# relayBoard.net
KiCad netlist of a schematic drawn in EAGLE
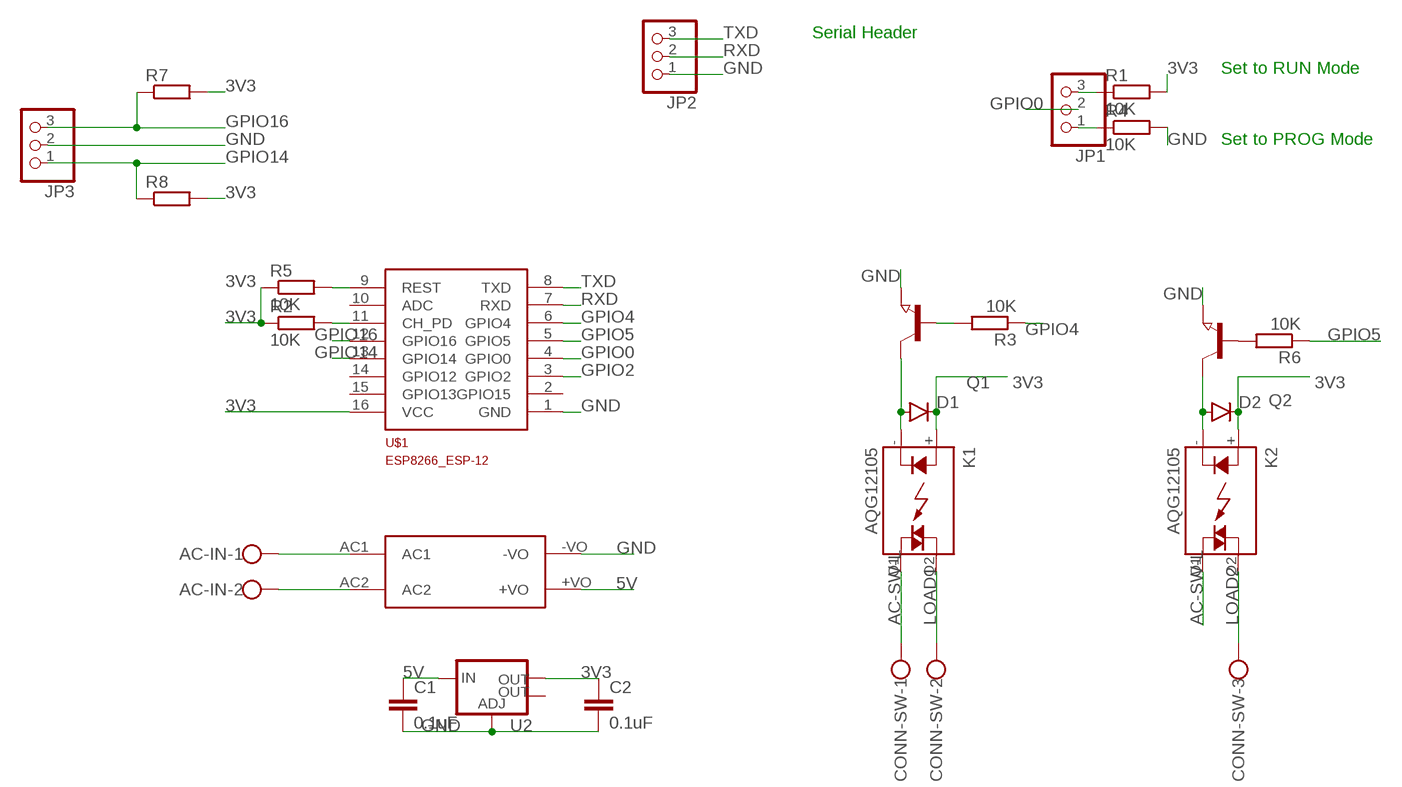
[diagram p0: schematic, sheet 1]

(export (version "E")
  (design (tool "Eeschema 10.0.6"))
  (components
    (comp (ref "AC-IN")
      (value "W237-102")
      (footprint "eagle-import:W237-102")
      (fields (field (name "MPN") "237-102"))
      (libsource (lib "eagle-import") (part "W237-102"))
    )
    (comp (ref "C1")
      (value "0.1uF")
      (footprint "eagle-import:0603-CAP")
      (libsource (lib "eagle-import") (part "0.1UF-25V-5%(0603)"))
    )
    (comp (ref "C2")
      (value "0.1uF")
      (footprint "eagle-import:0603-CAP")
      (libsource (lib "eagle-import") (part "0.1UF-25V-5%(0603)"))
    )
    (comp (ref "CONN-SW")
      (value "W237-103")
      (footprint "eagle-import:W237-103")
      (fields (field (name "MPN") "237-103"))
      (libsource (lib "eagle-import") (part "W237-103"))
    )
    (comp (ref "D1")
      (value "DIODESMA")
      (footprint "eagle-import:SMA-DIODE")
      (libsource (lib "eagle-import") (part "DIODESMA"))
    )
    (comp (ref "D2")
      (value "DIODESMA")
      (footprint "eagle-import:SMA-DIODE")
      (libsource (lib "eagle-import") (part "DIODESMA"))
    )
    (comp (ref "JP1")
      (value "PINHD-1X3")
      (footprint "eagle-import:1X03")
      (libsource (lib "eagle-import") (part "PINHD-1X3"))
    )
    (comp (ref "JP2")
      (value "PINHD-1X3")
      (footprint "eagle-import:1X03")
      (libsource (lib "eagle-import") (part "PINHD-1X3"))
    )
    (comp (ref "JP3")
      (value "PINHD-1X3")
      (footprint "eagle-import:1X03")
      (libsource (lib "eagle-import") (part "PINHD-1X3"))
    )
    (comp (ref "K1")
      (value "AQG12105")
      (footprint "eagle-import:AQG")
      (fields (field (name "MF") "AROMAT/ MATSUSHITA"))
      (libsource (lib "eagle-import") (part "AQG12105"))
    )
    (comp (ref "K2")
      (value "AQG12105")
      (footprint "eagle-import:AQG")
      (fields (field (name "MF") "AROMAT/ MATSUSHITA"))
      (libsource (lib "eagle-import") (part "AQG12105"))
    )
    (comp (ref "Q1")
      (value "NPN-TRANSISTOR_SOT23")
      (footprint "eagle-import:SOT23")
      (libsource (lib "eagle-import") (part "NPN-TRANSISTOR_SOT23"))
    )
    (comp (ref "Q2")
      (value "NPN-TRANSISTOR_SOT23")
      (footprint "eagle-import:SOT23")
      (libsource (lib "eagle-import") (part "NPN-TRANSISTOR_SOT23"))
    )
    (comp (ref "R1")
      (value "10K")
      (footprint "eagle-import:R0805")
      (libsource (lib "eagle-import") (part "R-EU_R0805"))
    )
    (comp (ref "R2")
      (value "10K")
      (footprint "eagle-import:R0805")
      (libsource (lib "eagle-import") (part "R-EU_R0805"))
    )
    (comp (ref "R3")
      (value "10K")
      (footprint "eagle-import:R0805")
      (libsource (lib "eagle-import") (part "R-EU_R0805"))
    )
    (comp (ref "R4")
      (value "10K")
      (footprint "eagle-import:R0805")
      (libsource (lib "eagle-import") (part "R-EU_R0805"))
    )
    (comp (ref "R5")
      (value "10K")
      (footprint "eagle-import:R0805")
      (libsource (lib "eagle-import") (part "R-EU_R0805"))
    )
    (comp (ref "R6")
      (value "10K")
      (footprint "eagle-import:R0805")
      (libsource (lib "eagle-import") (part "R-EU_R0805"))
    )
    (comp (ref "R7")
      (value "R-EU_R0805")
      (footprint "eagle-import:R0805")
      (libsource (lib "eagle-import") (part "R-EU_R0805"))
    )
    (comp (ref "R8")
      (value "R-EU_R0805")
      (footprint "eagle-import:R0805")
      (libsource (lib "eagle-import") (part "R-EU_R0805"))
    )
    (comp (ref "U$1")
      (value "ESP8266_ESP-12")
      (footprint "eagle-import:ESP8266-ESP12")
      (libsource (lib "eagle-import") (part "ESP8266_ESP-12"))
    )
    (comp (ref "U$4")
      (value "HLK-PM01")
      (footprint "eagle-import:HLK-PM01")
      (libsource (lib "eagle-import") (part "HLK-PM01"))
    )
    (comp (ref "U2")
      (value "V_REG_LM1117SOT223")
      (footprint "eagle-import:SOT223")
      (libsource (lib "eagle-import") (part "V_REG_LM1117SOT223"))
    )
  )
  (nets
    (net (code "1") (name "/3V3") (class "Default")
      (node (ref "C2") (pin "1") (pinfunction "1_1") (pintype "passive"))
      (node (ref "D1") (pin "C") (pinfunction "C_C") (pintype "passive"))
      (node (ref "D2") (pin "C") (pinfunction "C_C") (pintype "passive"))
      (node (ref "K1") (pin "+") (pinfunction "A_+") (pintype "passive"))
      (node (ref "K2") (pin "+") (pinfunction "A_+") (pintype "passive"))
      (node (ref "R1") (pin "2") (pinfunction "2_2") (pintype "passive"))
      (node (ref "R2") (pin "1") (pinfunction "1_1") (pintype "passive"))
      (node (ref "R5") (pin "1") (pinfunction "1_1") (pintype "passive"))
      (node (ref "R7") (pin "2") (pinfunction "2_2") (pintype "passive"))
      (node (ref "R8") (pin "2") (pinfunction "2_2") (pintype "passive"))
      (node (ref "U$1") (pin "16") (pinfunction "VCC_16") (pintype "bidirectional"))
      (node (ref "U2") (pin "2") (pinfunction "OUT_2") (pintype "output"))
    )
    (net (code "2") (name "/5V") (class "Default")
      (node (ref "C1") (pin "1") (pinfunction "1_1") (pintype "passive"))
      (node (ref "U$4") (pin "+VO") (pinfunction "+VO_+VO") (pintype "bidirectional"))
      (node (ref "U2") (pin "3") (pinfunction "IN_3") (pintype "input"))
    )
    (net (code "3") (name "/AC-SW-L") (class "Default")
      (node (ref "CONN-SW") (pin "1") (pinfunction "KL_1") (pintype "passive"))
      (node (ref "K1") (pin "O1") (pinfunction "DS2_O1") (pintype "passive"))
      (node (ref "K2") (pin "O1") (pinfunction "DS2_O1") (pintype "passive"))
    )
    (net (code "4") (name "/GND") (class "Default")
      (node (ref "C1") (pin "2") (pinfunction "2_2") (pintype "passive"))
      (node (ref "C2") (pin "2") (pinfunction "2_2") (pintype "passive"))
      (node (ref "JP2") (pin "1") (pinfunction "1_1") (pintype "passive"))
      (node (ref "JP3") (pin "2") (pinfunction "2_2") (pintype "passive"))
      (node (ref "Q1") (pin "2") (pinfunction "E_2") (pintype "passive"))
      (node (ref "Q2") (pin "2") (pinfunction "E_2") (pintype "passive"))
      (node (ref "R4") (pin "2") (pinfunction "2_2") (pintype "passive"))
      (node (ref "U$1") (pin "1") (pinfunction "GND_1") (pintype "bidirectional"))
      (node (ref "U$4") (pin "-VO") (pinfunction "-VO_-VO") (pintype "bidirectional"))
      (node (ref "U2") (pin "1") (pinfunction "ADJ_1") (pintype "input"))
    )
    (net (code "5") (name "/GPIO0") (class "Default")
      (node (ref "JP1") (pin "2") (pinfunction "2_2") (pintype "passive"))
      (node (ref "U$1") (pin "4") (pinfunction "GPIO0_4") (pintype "bidirectional"))
    )
    (net (code "6") (name "/GPIO2") (class "Default")
      (node (ref "U$1") (pin "3") (pinfunction "GPIO2_3") (pintype "bidirectional"))
    )
    (net (code "7") (name "/GPIO4") (class "Default")
      (node (ref "R3") (pin "1") (pinfunction "1_1") (pintype "passive"))
      (node (ref "U$1") (pin "6") (pinfunction "GPIO4_6") (pintype "bidirectional"))
    )
    (net (code "8") (name "/GPIO5") (class "Default")
      (node (ref "R6") (pin "1") (pinfunction "1_1") (pintype "passive"))
      (node (ref "U$1") (pin "5") (pinfunction "GPIO5_5") (pintype "bidirectional"))
    )
    (net (code "9") (name "/GPIO14") (class "Default")
      (node (ref "JP3") (pin "1") (pinfunction "1_1") (pintype "passive"))
      (node (ref "R8") (pin "1") (pinfunction "1_1") (pintype "passive"))
      (node (ref "U$1") (pin "13") (pinfunction "GPIO14_13") (pintype "bidirectional"))
    )
    (net (code "10") (name "/GPIO16") (class "Default")
      (node (ref "JP3") (pin "3") (pinfunction "3_3") (pintype "passive"))
      (node (ref "R7") (pin "1") (pinfunction "1_1") (pintype "passive"))
      (node (ref "U$1") (pin "12") (pinfunction "GPIO16_12") (pintype "bidirectional"))
    )
    (net (code "11") (name "/LOAD1") (class "Default")
      (node (ref "CONN-SW") (pin "2") (pinfunction "KL_2") (pintype "passive"))
      (node (ref "K1") (pin "O2") (pinfunction "DS1_O2") (pintype "passive"))
    )
    (net (code "12") (name "/LOAD2") (class "Default")
      (node (ref "CONN-SW") (pin "3") (pinfunction "KL_3") (pintype "passive"))
      (node (ref "K2") (pin "O2") (pinfunction "DS1_O2") (pintype "passive"))
    )
    (net (code "13") (name "/RXD") (class "Default")
      (node (ref "JP2") (pin "2") (pinfunction "2_2") (pintype "passive"))
      (node (ref "U$1") (pin "7") (pinfunction "RXD_7") (pintype "bidirectional"))
    )
    (net (code "14") (name "/TXD") (class "Default")
      (node (ref "JP2") (pin "3") (pinfunction "3_3") (pintype "passive"))
      (node (ref "U$1") (pin "8") (pinfunction "TXD_8") (pintype "bidirectional"))
    )
    (net (code "15") (name "Net-(AC-INA-KL)") (class "Default")
      (node (ref "AC-IN") (pin "1") (pinfunction "KL_1") (pintype "passive"))
      (node (ref "U$4") (pin "AC1") (pinfunction "AC1_AC1") (pintype "bidirectional"))
    )
    (net (code "16") (name "Net-(AC-INB-KL)") (class "Default")
      (node (ref "AC-IN") (pin "2") (pinfunction "KL_2") (pintype "passive"))
      (node (ref "U$4") (pin "AC2") (pinfunction "AC2_AC2") (pintype "bidirectional"))
    )
    (net (code "17") (name "Net-(JP1-Pad1)") (class "Default")
      (node (ref "JP1") (pin "1") (pinfunction "1_1") (pintype "passive"))
      (node (ref "R4") (pin "1") (pinfunction "1_1") (pintype "passive"))
    )
    (net (code "18") (name "Net-(JP1-Pad3)") (class "Default")
      (node (ref "JP1") (pin "3") (pinfunction "3_3") (pintype "passive"))
      (node (ref "R1") (pin "1") (pinfunction "1_1") (pintype "passive"))
    )
    (net (code "19") (name "Net-(K1-K)") (class "Default")
      (node (ref "D1") (pin "A") (pinfunction "A_A") (pintype "passive"))
      (node (ref "K1") (pin "-") (pinfunction "K_-") (pintype "passive"))
      (node (ref "Q1") (pin "3") (pinfunction "C_3") (pintype "passive"))
    )
    (net (code "20") (name "Net-(K2-K)") (class "Default")
      (node (ref "D2") (pin "A") (pinfunction "A_A") (pintype "passive"))
      (node (ref "K2") (pin "-") (pinfunction "K_-") (pintype "passive"))
      (node (ref "Q2") (pin "3") (pinfunction "C_3") (pintype "passive"))
    )
    (net (code "21") (name "Net-(Q1-B)") (class "Default")
      (node (ref "Q1") (pin "1") (pinfunction "B_1") (pintype "passive"))
      (node (ref "R3") (pin "2") (pinfunction "2_2") (pintype "passive"))
    )
    (net (code "22") (name "Net-(Q2-B)") (class "Default")
      (node (ref "Q2") (pin "1") (pinfunction "B_1") (pintype "passive"))
      (node (ref "R6") (pin "2") (pinfunction "2_2") (pintype "passive"))
    )
    (net (code "23") (name "Net-(U$1-CH_PD)") (class "Default")
      (node (ref "R2") (pin "2") (pinfunction "2_2") (pintype "passive"))
      (node (ref "U$1") (pin "11") (pinfunction "CH_PD_11") (pintype "bidirectional"))
    )
    (net (code "24") (name "Net-(U$1-REST)") (class "Default")
      (node (ref "R5") (pin "2") (pinfunction "2_2") (pintype "passive"))
      (node (ref "U$1") (pin "9") (pinfunction "REST_9") (pintype "bidirectional"))
    )
    (net (code "25") (name "unconnected-(U$1-ADC-Pad10)") (class "Default")
      (node (ref "U$1") (pin "10") (pinfunction "ADC_10") (pintype "bidirectional"))
    )
    (net (code "26") (name "unconnected-(U$1-GPIO12-Pad14)") (class "Default")
      (node (ref "U$1") (pin "14") (pinfunction "GPIO12_14") (pintype "bidirectional"))
    )
    (net (code "27") (name "unconnected-(U$1-GPIO13-Pad15)") (class "Default")
      (node (ref "U$1") (pin "15") (pinfunction "GPIO13_15") (pintype "bidirectional"))
    )
    (net (code "28") (name "unconnected-(U$1-GPIO15-Pad2)") (class "Default")
      (node (ref "U$1") (pin "2") (pinfunction "GPIO15_2") (pintype "bidirectional"))
    )
    (net (code "29") (name "unconnected-(U2-OUT-Pad4)") (class "Default")
      (node (ref "U2") (pin "4") (pinfunction "OUT_4") (pintype "output"))
    )
  )
)
